# Sensing_-_Voltage.net
KiCad netlist of a schematic drawn in Altium Designer
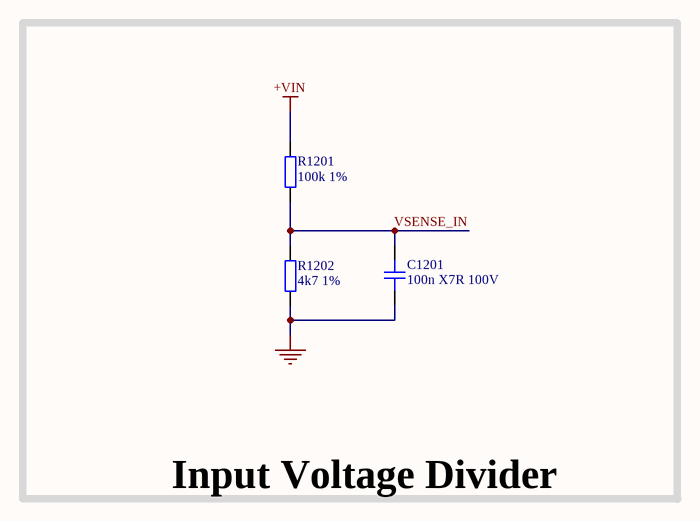
[diagram p0: Sensing - Voltage.SchDoc]

(export (version "E")
  (design (tool "Eeschema 10.0.6"))
  (components
    (comp (ref "C1201")
      (value "100n X7R 100V")
      (footprint "CAP_0603")
      (description "Capacitor SMD 0603")
      (fields
        (field (name "MANUFACTURER") "CCTC")
        (field (name "MANUFACTURER PART NUMBER") "TCC0603X7R104K101CT")
      )
      (libsource (lib "Schematic-Lib-PhilsLab") (part "CAP_0603"))
    )
    (comp (ref "R1201")
      (value "100k 1%")
      (footprint "RES_0603")
      (description "Resistor SMD 0603")
      (fields
        (field (name "MANUFACTURER") "Vishay Intertech")
        (field (name "MANUFACTURER PART NUMBER") "MCT06030C1003FP500")
      )
      (libsource (lib "Schematic-Lib-PhilsLab") (part "RES_0603"))
    )
    (comp (ref "R1202")
      (value "4k7 1%")
      (footprint "RES_0603")
      (description "Resistor SMD 0603")
      (fields
        (field (name "MANUFACTURER") "Vishay Intertech")
        (field (name "MANUFACTURER PART NUMBER") "TNPW06034K70BEEA")
      )
      (libsource (lib "Schematic-Lib-PhilsLab") (part "RES_0603"))
    )
  )
  (nets
    (net (code "1") (name "+VIN") (class "Default")
      (node (ref "R1201") (pin "2") (pinfunction "2_2") (pintype "passive"))
    )
    (net (code "2") (name "/VSENSE_IN") (class "Default")
      (node (ref "C1201") (pin "2") (pinfunction "2_2") (pintype "passive"))
      (node (ref "R1201") (pin "1") (pinfunction "1_1") (pintype "passive"))
      (node (ref "R1202") (pin "2") (pinfunction "2_2") (pintype "passive"))
    )
    (net (code "3") (name "GND") (class "Default")
      (node (ref "C1201") (pin "1") (pinfunction "1_1") (pintype "passive"))
      (node (ref "R1202") (pin "1") (pinfunction "1_1") (pintype "passive"))
    )
  )
)
